# rf.net
KiCad netlist of a schematic drawn in Altium Designer
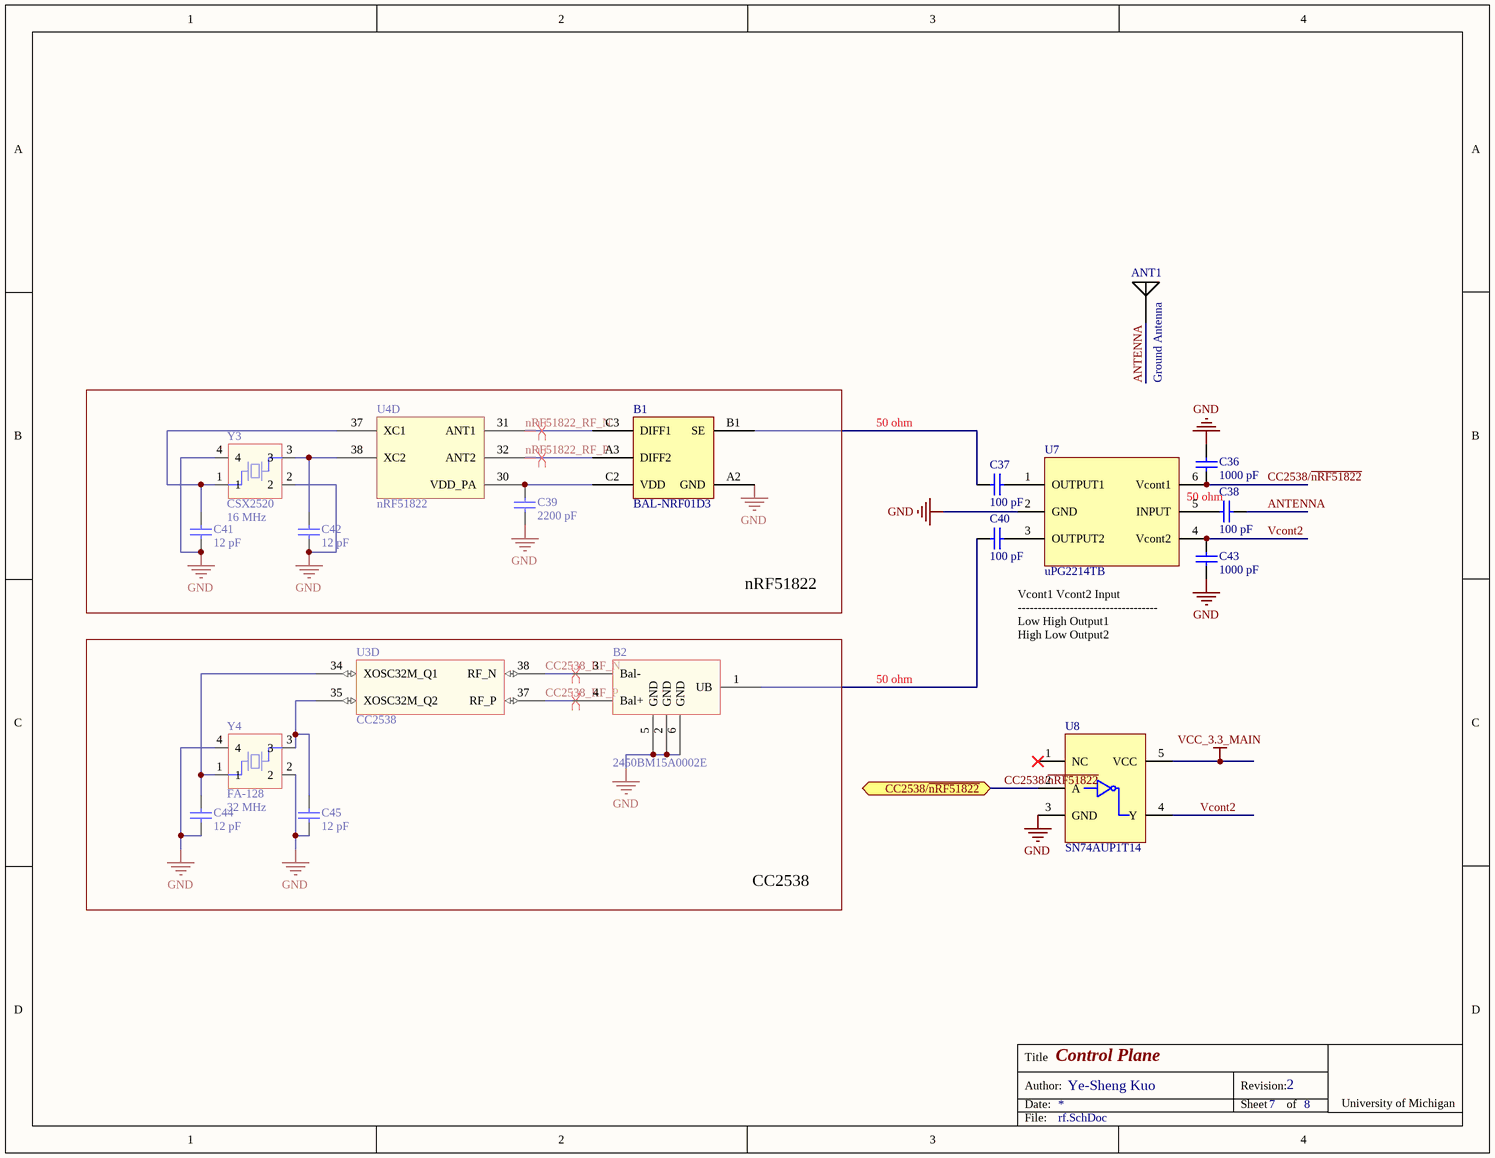
[diagram p0: rf.SchDoc]

(export (version "E")
  (design (tool "Eeschema 10.0.6"))
  (components
    (comp (ref "ANT1")
      (value "Ground Antenna")
      (footprint "Chip Antenna")
      (description "2.4GHz Surface Mount Device (SMD) On Ground Antenna, 50 Ohms")
      (libsource (lib "RF") (part "Ground Antenna"))
    )
    (comp (ref "B1")
      (value "BAL-NRF01D3")
      (footprint "BAL-NRF01D3")
      (description "50 ohm nominal input / conjugate match balun to nRF51822-CEAA")
      (libsource (lib "RF") (part "BAL-NRF01D3"))
    )
    (comp (ref "B2")
      (value "2450BM15A0002E")
      (footprint "2450BM15A0002")
      (description "2.45 GHz Balun for TI CC253X")
      (libsource (lib "sdl") (part "2450BM15A0002E"))
    )
    (comp (ref "C36")
      (value "1000 pF")
      (footprint "0402")
      (description "Ceramic capacitor, 1000 pF, 0402 package")
      (fields (field (name "TOLERANCE") "10%") (field (name "Comment") "Ceramic capacitor"))
      (libsource (lib "rlc") (part "C_1000p_50V_0402_ceramic"))
    )
    (comp (ref "C37")
      (value "100 pF")
      (footprint "0402")
      (description "Ceramic capacitor, 100 pF, 0402 package")
      (fields (field (name "TOLERANCE") "1%") (field (name "Comment") "Ceramic capacitor"))
      (libsource (lib "rlc") (part "C_100p_25V_0402_ceramic"))
    )
    (comp (ref "C38")
      (value "100 pF")
      (footprint "0402")
      (description "Ceramic capacitor, 100 pF, 0402 package")
      (fields (field (name "TOLERANCE") "1%") (field (name "Comment") "Ceramic capacitor"))
      (libsource (lib "rlc") (part "C_100p_25V_0402_ceramic"))
    )
    (comp (ref "C39")
      (value "2200 pF")
      (footprint "0402")
      (description "Ceramic capacitor, 2200 pF, 0402 package")
      (fields (field (name "TOLERANCE") "10%") (field (name "Comment") "Ceramic capacitor"))
      (libsource (lib "rlc") (part "C_2200p_50V_0402_ceramic"))
    )
    (comp (ref "C40")
      (value "100 pF")
      (footprint "0402")
      (description "Ceramic capacitor, 100 pF, 0402 package")
      (fields (field (name "TOLERANCE") "1%") (field (name "Comment") "Ceramic capacitor"))
      (libsource (lib "rlc") (part "C_100p_25V_0402_ceramic"))
    )
    (comp (ref "C41")
      (value "12 pF")
      (footprint "0402")
      (description "Ceramic capacitor, 12 pF, 0402 package")
      (fields (field (name "TOLERANCE") "2%") (field (name "Comment") "Ceramic capacitor"))
      (libsource (lib "rlc") (part "C_12p_0402_ceramic"))
    )
    (comp (ref "C42")
      (value "12 pF")
      (footprint "0402")
      (description "Ceramic capacitor, 12 pF, 0402 package")
      (fields (field (name "TOLERANCE") "2%") (field (name "Comment") "Ceramic capacitor"))
      (libsource (lib "rlc") (part "C_12p_0402_ceramic"))
    )
    (comp (ref "C43")
      (value "1000 pF")
      (footprint "0402")
      (description "Ceramic capacitor, 1000 pF, 0402 package")
      (fields (field (name "TOLERANCE") "10%") (field (name "Comment") "Ceramic capacitor"))
      (libsource (lib "rlc") (part "C_1000p_50V_0402_ceramic"))
    )
    (comp (ref "C44")
      (value "12 pF")
      (footprint "0402")
      (description "Ceramic capacitor, 12 pF, 0402 package")
      (fields (field (name "TOLERANCE") "2%") (field (name "Comment") "Ceramic capacitor"))
      (libsource (lib "rlc") (part "C_12p_0402_ceramic"))
    )
    (comp (ref "C45")
      (value "12 pF")
      (footprint "0402")
      (description "Ceramic capacitor, 12 pF, 0402 package")
      (fields (field (name "TOLERANCE") "2%") (field (name "Comment") "Ceramic capacitor"))
      (libsource (lib "rlc") (part "C_12p_0402_ceramic"))
    )
    (comp (ref "U3")
      (value "CC2538")
      (footprint "QFN56")
      (description "A Powerful System-On-Chip for 2.4-GHz IEEE 802.15.4, 6LoWPAN  and ZigBee Applications")
      (libsource (lib "sdl") (part "CC2538"))
    )
    (comp (ref "U4")
      (value "nRF51822")
      (footprint "QFN-48")
      (description "Multiprotocol Bluetooth® low energy/2.4 GHz RF System on Chip")
      (libsource (lib "sdl") (part "nRF51822"))
    )
    (comp (ref "U7")
      (value "uPG2214TB")
      (footprint "minimold-6")
      (description "GaAs Integrated Circuit for L, S-Band SPDT Switch")
      (libsource (lib "RF") (part "uPG2214TB"))
    )
    (comp (ref "U8")
      (value "SN74AUP1T14")
      (footprint "SC-70-5 (DCK)")
      (description "LOW POWER, 1.8/2.5/3.3-V INPUT, 3.3-V CMOS OUTPUT, SINGLE  SCHMITT-TRIGGER INVERTER GATE")
      (libsource (lib "logics") (part "SN74AUP1T14"))
    )
    (comp (ref "Y3")
      (value "CSX2520")
      (footprint "CX2520")
      (description "Crystal oscillator")
      (fields (field (name "FREQUENCY") "16 MHz"))
      (libsource (lib "crystal_oscillators_rtc") (part "CSX2520"))
    )
    (comp (ref "Y4")
      (value "FA-128")
      (footprint "FA-128")
      (description "MHz Range Crystal Unit")
      (fields (field (name "FREQUENCY") "32 MHz"))
      (libsource (lib "crystal_oscillators_rtc") (part "FA-128"))
    )
  )
  (nets
    (net (code "1") (name "/ANTENNA") (class "Default")
      (node (ref "ANT1") (pin "1") (pintype "passive"))
      (node (ref "C38") (pin "2") (pintype "passive"))
    )
    (net (code "2") (name "/CC2538_RF_N") (class "Default")
      (node (ref "B2") (pin "3") (pinfunction "Bal-_3") (pintype "passive"))
      (node (ref "U3") (pin "38") (pinfunction "RF_N_38") (pintype "bidirectional"))
    )
    (net (code "3") (name "/CC2538_RF_P") (class "Default")
      (node (ref "B2") (pin "4") (pinfunction "Bal+_4") (pintype "passive"))
      (node (ref "U3") (pin "37") (pinfunction "RF_P_37") (pintype "bidirectional"))
    )
    (net (code "4") (name "/CC2538{slash}~{nRF51822}") (class "Default")
      (node (ref "C36") (pin "2") (pintype "passive"))
      (node (ref "U7") (pin "6") (pinfunction "Vcont1_6") (pintype "power_in"))
      (node (ref "U8") (pin "2") (pinfunction "A_2") (pintype "power_in"))
    )
    (net (code "5") (name "/Vcont2") (class "Default")
      (node (ref "C43") (pin "1") (pintype "passive"))
      (node (ref "U7") (pin "4") (pinfunction "Vcont2_4") (pintype "power_in"))
      (node (ref "U8") (pin "4") (pinfunction "Y_4") (pintype "power_in"))
    )
    (net (code "6") (name "/nRF51822_RF_N") (class "Default")
      (node (ref "B1") (pin "C3") (pinfunction "DIFF1_C3") (pintype "passive"))
      (node (ref "U4") (pin "31") (pinfunction "ANT1_31") (pintype "passive"))
    )
    (net (code "7") (name "/nRF51822_RF_P") (class "Default")
      (node (ref "B1") (pin "A3") (pinfunction "DIFF2_A3") (pintype "passive"))
      (node (ref "U4") (pin "32") (pinfunction "ANT2_32") (pintype "passive"))
    )
    (net (code "8") (name "GND") (class "Default")
      (node (ref "B1") (pin "A2") (pinfunction "GND_A2") (pintype "passive"))
      (node (ref "B2") (pin "2") (pinfunction "GND_2") (pintype "passive"))
      (node (ref "B2") (pin "5") (pinfunction "GND_5") (pintype "passive"))
      (node (ref "B2") (pin "6") (pinfunction "GND_6") (pintype "passive"))
      (node (ref "C36") (pin "1") (pintype "passive"))
      (node (ref "C39") (pin "2") (pintype "passive"))
      (node (ref "C41") (pin "1") (pintype "passive"))
      (node (ref "C42") (pin "1") (pintype "passive"))
      (node (ref "C43") (pin "2") (pintype "passive"))
      (node (ref "C44") (pin "1") (pintype "passive"))
      (node (ref "C45") (pin "1") (pintype "passive"))
      (node (ref "U7") (pin "2") (pinfunction "GND_2") (pintype "power_in"))
      (node (ref "U8") (pin "3") (pinfunction "GND_3") (pintype "power_in"))
      (node (ref "Y3") (pin "2") (pinfunction "2_2") (pintype "passive"))
      (node (ref "Y3") (pin "4") (pinfunction "4_4") (pintype "passive"))
      (node (ref "Y4") (pin "2") (pinfunction "2_2") (pintype "passive"))
      (node (ref "Y4") (pin "4") (pinfunction "4_4") (pintype "passive"))
    )
    (net (code "9") (name "Net-(B1-SE)") (class "Default")
      (node (ref "B1") (pin "B1") (pinfunction "SE_B1") (pintype "passive"))
      (node (ref "C37") (pin "1") (pintype "passive"))
    )
    (net (code "10") (name "Net-(B1-VDD)") (class "Default")
      (node (ref "B1") (pin "C2") (pinfunction "VDD_C2") (pintype "passive"))
      (node (ref "C39") (pin "1") (pintype "passive"))
      (node (ref "U4") (pin "30") (pinfunction "VDD_PA_30") (pintype "passive"))
    )
    (net (code "11") (name "Net-(B2-UB)") (class "Default")
      (node (ref "B2") (pin "1") (pinfunction "UB_1") (pintype "passive"))
      (node (ref "C40") (pin "1") (pintype "passive"))
    )
    (net (code "12") (name "Net-(U3D-XOSC32M_Q1)") (class "Default")
      (node (ref "C44") (pin "2") (pintype "passive"))
      (node (ref "U3") (pin "34") (pinfunction "XOSC32M_Q1_34") (pintype "bidirectional"))
      (node (ref "Y4") (pin "1") (pinfunction "1_1") (pintype "passive"))
    )
    (net (code "13") (name "Net-(U3D-XOSC32M_Q2)") (class "Default")
      (node (ref "C45") (pin "2") (pintype "passive"))
      (node (ref "U3") (pin "35") (pinfunction "XOSC32M_Q2_35") (pintype "bidirectional"))
      (node (ref "Y4") (pin "3") (pinfunction "3_3") (pintype "passive"))
    )
    (net (code "14") (name "Net-(U4D-XC1)") (class "Default")
      (node (ref "C41") (pin "2") (pintype "passive"))
      (node (ref "U4") (pin "37") (pinfunction "XC1_37") (pintype "passive"))
      (node (ref "Y3") (pin "1") (pinfunction "1_1") (pintype "passive"))
    )
    (net (code "15") (name "Net-(U4D-XC2)") (class "Default")
      (node (ref "C42") (pin "2") (pintype "passive"))
      (node (ref "U4") (pin "38") (pinfunction "XC2_38") (pintype "passive"))
      (node (ref "Y3") (pin "3") (pinfunction "3_3") (pintype "passive"))
    )
    (net (code "16") (name "Net-(U7-INPUT)") (class "Default")
      (node (ref "C38") (pin "1") (pintype "passive"))
      (node (ref "U7") (pin "5") (pinfunction "INPUT_5") (pintype "power_in"))
    )
    (net (code "17") (name "Net-(U7-OUTPUT1)") (class "Default")
      (node (ref "C37") (pin "2") (pintype "passive"))
      (node (ref "U7") (pin "1") (pinfunction "OUTPUT1_1") (pintype "power_in"))
    )
    (net (code "18") (name "Net-(U7-OUTPUT2)") (class "Default")
      (node (ref "C40") (pin "2") (pintype "passive"))
      (node (ref "U7") (pin "3") (pinfunction "OUTPUT2_3") (pintype "power_in"))
    )
    (net (code "19") (name "VCC_3.3_MAIN") (class "Default")
      (node (ref "U8") (pin "5") (pinfunction "VCC_5") (pintype "power_in"))
    )
    (net (code "20") (name "unconnected-(U8-NC-Pad1)") (class "Default")
      (node (ref "U8") (pin "1") (pinfunction "NC_1") (pintype "power_in+no_connect"))
    )
  )
)
